# 12V_Converter.net
KiCad netlist of a schematic drawn in Altium Designer
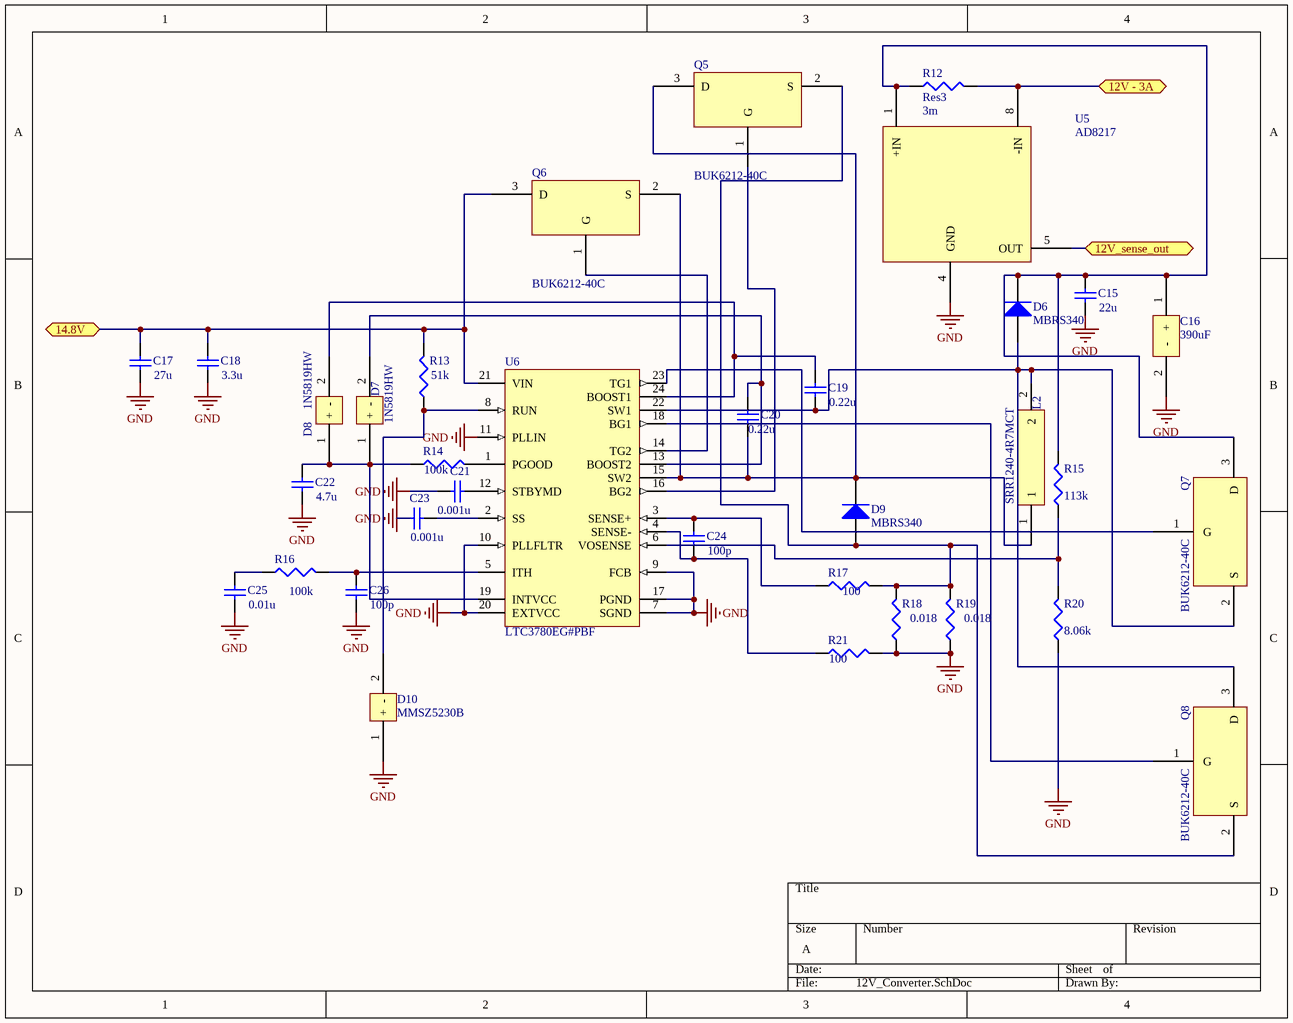
[diagram p0: 12V_Converter.SchDoc]

(export (version "E")
  (design (tool "Eeschema 10.0.6"))
  (components
    (comp (ref "C15")
      (value "22u")
      (footprint "C1206")
      (description "Capacitor (Semiconductor SIM Model)")
      (fields (field (name "Comment") "Cap Semi") (field (name "PUBLISHER") "Altium Limited"))
      (libsource (lib "Miscellaneous Devices") (part "Cap Semi"))
    )
    (comp (ref "C16")
      (value "390uF")
      (footprint "PCV1E391MCL2GS")
      (description "Aluminum Capacitor")
      (libsource (lib "Integrated_Library") (part "PCV1E391MCL2GS"))
    )
    (comp (ref "C17")
      (value "27u")
      (footprint "C1206")
      (description "Capacitor (Semiconductor SIM Model)")
      (fields (field (name "Comment") "Cap Semi") (field (name "PUBLISHER") "Altium Limited"))
      (libsource (lib "Miscellaneous Devices") (part "Cap Semi"))
    )
    (comp (ref "C18")
      (value "3.3u")
      (footprint "C1206")
      (description "Capacitor (Semiconductor SIM Model)")
      (fields (field (name "Comment") "Cap Semi") (field (name "PUBLISHER") "Altium Limited"))
      (libsource (lib "Miscellaneous Devices") (part "Cap Semi"))
    )
    (comp (ref "C19")
      (value "0.22u")
      (footprint "C1206")
      (description "Capacitor (Semiconductor SIM Model)")
      (fields (field (name "Comment") "Cap Semi") (field (name "PUBLISHER") "Altium Limited"))
      (libsource (lib "Miscellaneous Devices") (part "Cap Semi"))
    )
    (comp (ref "C20")
      (value "0.22u")
      (footprint "C1206")
      (description "Capacitor (Semiconductor SIM Model)")
      (fields (field (name "Comment") "Cap Semi") (field (name "PUBLISHER") "Altium Limited"))
      (libsource (lib "Miscellaneous Devices") (part "Cap Semi"))
    )
    (comp (ref "C21")
      (value "0.001u")
      (footprint "C1206")
      (description "Capacitor (Semiconductor SIM Model)")
      (fields (field (name "Comment") "Cap Semi") (field (name "PUBLISHER") "Altium Limited"))
      (libsource (lib "Miscellaneous Devices") (part "Cap Semi"))
    )
    (comp (ref "C22")
      (value "4.7u")
      (footprint "C1206")
      (description "Capacitor (Semiconductor SIM Model)")
      (fields (field (name "Comment") "Cap Semi") (field (name "PUBLISHER") "Altium Limited"))
      (libsource (lib "Miscellaneous Devices") (part "Cap Semi"))
    )
    (comp (ref "C23")
      (value "0.001u")
      (footprint "C1206")
      (description "Capacitor (Semiconductor SIM Model)")
      (fields (field (name "Comment") "Cap Semi") (field (name "PUBLISHER") "Altium Limited"))
      (libsource (lib "Miscellaneous Devices") (part "Cap Semi"))
    )
    (comp (ref "C24")
      (value "100p")
      (footprint "C1206")
      (description "Capacitor (Semiconductor SIM Model)")
      (fields (field (name "Comment") "Cap Semi") (field (name "PUBLISHER") "Altium Limited"))
      (libsource (lib "Miscellaneous Devices") (part "Cap Semi"))
    )
    (comp (ref "C25")
      (value "0.01u")
      (footprint "C1206")
      (description "Capacitor (Semiconductor SIM Model)")
      (fields (field (name "Comment") "Cap Semi") (field (name "PUBLISHER") "Altium Limited"))
      (libsource (lib "Miscellaneous Devices") (part "Cap Semi"))
    )
    (comp (ref "C26")
      (value "100p")
      (footprint "C1206")
      (description "Capacitor (Semiconductor SIM Model)")
      (fields (field (name "Comment") "Cap Semi") (field (name "PUBLISHER") "Altium Limited"))
      (libsource (lib "Miscellaneous Devices") (part "Cap Semi"))
    )
    (comp (ref "D6")
      (value "MBRS340")
      (footprint "SMC")
      (description "Default Diode")
      (fields (field (name "PUBLISHER") "Altium Limited"))
      (libsource (lib "Miscellaneous Devices") (part "Diode"))
    )
    (comp (ref "D7")
      (value "1N5819HW")
      (footprint "1N5819HW")
      (description "1A Schottky Barrier Rectifier")
      (libsource (lib "Integrated_Library") (part "1N5819HW"))
    )
    (comp (ref "D8")
      (value "1N5819HW")
      (footprint "1N5819HW")
      (description "1A Schottky Barrier Rectifier")
      (libsource (lib "Integrated_Library") (part "1N5819HW"))
    )
    (comp (ref "D9")
      (value "MBRS340")
      (footprint "SMC")
      (description "Default Diode")
      (fields (field (name "PUBLISHER") "Altium Limited"))
      (libsource (lib "Miscellaneous Devices") (part "Diode"))
    )
    (comp (ref "D10")
      (value "MMSZ5230B")
      (footprint "MMSZ5230B")
      (description "Zener Diode")
      (libsource (lib "Integrated_Library") (part "MMSZ5230B"))
    )
    (comp (ref "L2")
      (value "SRR1240-4R7MCT")
      (footprint "SRR1240-4R7M")
      (description "Inductor")
      (libsource (lib "Integrated_Library") (part "SRR1240-4R7MCT"))
    )
    (comp (ref "Q5")
      (value "BUK6212-40C")
      (footprint "BUK6212-40C")
      (description "N-Channel TrenchMOS Intermediate Level FET")
      (libsource (lib "Integrated_Library") (part "BUK6212-40C"))
    )
    (comp (ref "Q6")
      (value "BUK6212-40C")
      (footprint "BUK6212-40C")
      (description "N-Channel TrenchMOS Intermediate Level FET")
      (libsource (lib "Integrated_Library") (part "BUK6212-40C"))
    )
    (comp (ref "Q7")
      (value "BUK6212-40C")
      (footprint "BUK6212-40C")
      (description "N-Channel TrenchMOS Intermediate Level FET")
      (libsource (lib "") (part "BUK6212-40C_1"))
    )
    (comp (ref "Q8")
      (value "BUK6212-40C")
      (footprint "BUK6212-40C")
      (description "N-Channel TrenchMOS Intermediate Level FET")
      (libsource (lib "") (part "BUK6212-40C_1"))
    )
    (comp (ref "R12")
      (value "Res3")
      (footprint "14-1210")
      (description "Resistor")
      (fields (field (name "ALTIUM_VALUE") "3m") (field (name "PUBLISHER") "Altium Limited"))
      (libsource (lib "Miscellaneous Devices") (part "Res3"))
    )
    (comp (ref "R13")
      (value "51k")
      (footprint "J1-0603")
      (description "Resistor")
      (fields (field (name "Comment") "Res3") (field (name "PUBLISHER") "Altium Limited"))
      (libsource (lib "Miscellaneous Devices") (part "Res3"))
    )
    (comp (ref "R14")
      (value "100k")
      (footprint "J1-0603")
      (description "Resistor")
      (fields (field (name "Comment") "Res3") (field (name "PUBLISHER") "Altium Limited"))
      (libsource (lib "Miscellaneous Devices") (part "Res3"))
    )
    (comp (ref "R15")
      (value "113k")
      (footprint "J1-0603")
      (description "Resistor")
      (fields (field (name "Comment") "Res3") (field (name "PUBLISHER") "Altium Limited"))
      (libsource (lib "Miscellaneous Devices") (part "Res3"))
    )
    (comp (ref "R16")
      (value "100k")
      (footprint "J1-0603")
      (description "Resistor")
      (fields (field (name "Comment") "Res3") (field (name "PUBLISHER") "Altium Limited"))
      (libsource (lib "Miscellaneous Devices") (part "Res3"))
    )
    (comp (ref "R17")
      (value "100")
      (footprint "J1-0603")
      (description "Resistor")
      (fields (field (name "Comment") "Res3") (field (name "PUBLISHER") "Altium Limited"))
      (libsource (lib "Miscellaneous Devices") (part "Res3"))
    )
    (comp (ref "R18")
      (value "0.018")
      (footprint "J1-0603")
      (description "Resistor")
      (fields (field (name "Comment") "Res3") (field (name "PUBLISHER") "Altium Limited"))
      (libsource (lib "Miscellaneous Devices") (part "Res3"))
    )
    (comp (ref "R19")
      (value "0.018")
      (footprint "J1-0603")
      (description "Resistor")
      (fields (field (name "Comment") "Res3") (field (name "PUBLISHER") "Altium Limited"))
      (libsource (lib "Miscellaneous Devices") (part "Res3"))
    )
    (comp (ref "R20")
      (value "8.06k")
      (footprint "J1-0603")
      (description "Resistor")
      (fields (field (name "Comment") "Res3") (field (name "PUBLISHER") "Altium Limited"))
      (libsource (lib "Miscellaneous Devices") (part "Res3"))
    )
    (comp (ref "R21")
      (value "100")
      (footprint "J1-0603")
      (description "Resistor")
      (fields (field (name "Comment") "Res3") (field (name "PUBLISHER") "Altium Limited"))
      (libsource (lib "Miscellaneous Devices") (part "Res3"))
    )
    (comp (ref "U5")
      (value "AD8217")
      (footprint "AD8217")
      (description "Current Shunt Moniter")
      (libsource (lib "Integrated_Library") (part "AD8217"))
    )
    (comp (ref "U6")
      (value "LTC3780EG#PBF")
      (footprint "LTC3780 24-Leaqd Plastic SSOP")
      (fields (field (name "MANUFACTURER") "Linear Technology"))
      (libsource (lib "Integrated_Library") (part "LTC3780EG#PBF"))
    )
  )
  (nets
    (net (code "1") (name "/12V - 3A") (class "Default")
      (node (ref "R12") (pin "2") (pinfunction "2_2") (pintype "passive"))
      (node (ref "U5") (pin "8") (pinfunction "-IN_8") (pintype "passive"))
    )
    (net (code "2") (name "/12V_sense_out") (class "Default")
      (node (ref "U5") (pin "5") (pinfunction "OUT_5") (pintype "passive"))
    )
    (net (code "3") (name "/14.8V") (class "Default")
      (node (ref "C17") (pin "2") (pinfunction "2_2") (pintype "passive"))
      (node (ref "C18") (pin "2") (pinfunction "2_2") (pintype "passive"))
      (node (ref "Q6") (pin "3") (pinfunction "D_3") (pintype "passive"))
      (node (ref "R13") (pin "2") (pinfunction "2_2") (pintype "passive"))
      (node (ref "U6") (pin "21") (pinfunction "VIN_21") (pintype "power_in"))
    )
    (net (code "4") (name "GND") (class "Default")
      (node (ref "C15") (pin "1") (pinfunction "1_1") (pintype "passive"))
      (node (ref "C16") (pin "2") (pinfunction "-_2") (pintype "passive"))
      (node (ref "C17") (pin "1") (pinfunction "1_1") (pintype "passive"))
      (node (ref "C18") (pin "1") (pinfunction "1_1") (pintype "passive"))
      (node (ref "C21") (pin "1") (pinfunction "1_1") (pintype "passive"))
      (node (ref "C22") (pin "1") (pinfunction "1_1") (pintype "passive"))
      (node (ref "C23") (pin "1") (pinfunction "1_1") (pintype "passive"))
      (node (ref "C25") (pin "1") (pinfunction "1_1") (pintype "passive"))
      (node (ref "C26") (pin "1") (pinfunction "1_1") (pintype "passive"))
      (node (ref "D10") (pin "1") (pinfunction "+_1") (pintype "passive"))
      (node (ref "R18") (pin "1") (pinfunction "1_1") (pintype "passive"))
      (node (ref "R19") (pin "1") (pinfunction "1_1") (pintype "passive"))
      (node (ref "R20") (pin "1") (pinfunction "1_1") (pintype "passive"))
      (node (ref "R21") (pin "2") (pinfunction "2_2") (pintype "passive"))
      (node (ref "U5") (pin "4") (pinfunction "GND_4") (pintype "passive"))
      (node (ref "U6") (pin "10") (pinfunction "PLLFLTR_10") (pintype "input"))
      (node (ref "U6") (pin "11") (pinfunction "PLLIN_11") (pintype "input"))
      (node (ref "U6") (pin "17") (pinfunction "PGND_17") (pintype "power_in"))
      (node (ref "U6") (pin "20") (pinfunction "EXTVCC_20") (pintype "power_in"))
      (node (ref "U6") (pin "7") (pinfunction "SGND_7") (pintype "power_in"))
      (node (ref "U6") (pin "9") (pinfunction "FCB_9") (pintype "input"))
    )
    (net (code "5") (name "Net-(C16-+)") (class "Default")
      (node (ref "C15") (pin "2") (pinfunction "2_2") (pintype "passive"))
      (node (ref "C16") (pin "1") (pinfunction "+_1") (pintype "passive"))
      (node (ref "D6") (pin "2") (pinfunction "K_2") (pintype "passive"))
      (node (ref "Q7") (pin "3") (pinfunction "D_3") (pintype "passive"))
      (node (ref "R12") (pin "1") (pinfunction "1_1") (pintype "passive"))
      (node (ref "R15") (pin "2") (pinfunction "2_2") (pintype "passive"))
      (node (ref "U5") (pin "1") (pinfunction "+IN_1") (pintype "passive"))
    )
    (net (code "6") (name "Net-(C25-Pad2)") (class "Default")
      (node (ref "C25") (pin "2") (pinfunction "2_2") (pintype "passive"))
      (node (ref "R16") (pin "1") (pinfunction "1_1") (pintype "passive"))
    )
    (net (code "7") (name "Net-(D6-A)") (class "Default")
      (node (ref "C19") (pin "1") (pinfunction "1_1") (pintype "passive"))
      (node (ref "D6") (pin "1") (pinfunction "A_1") (pintype "passive"))
      (node (ref "L2") (pin "2") (pinfunction "2_2") (pintype "passive"))
      (node (ref "Q7") (pin "2") (pinfunction "S_2") (pintype "passive"))
      (node (ref "Q8") (pin "3") (pinfunction "D_3") (pintype "passive"))
      (node (ref "U6") (pin "22") (pinfunction "SW1_22") (pintype "passive"))
    )
    (net (code "8") (name "Net-(D7-+)") (class "Default")
      (node (ref "C22") (pin "2") (pinfunction "2_2") (pintype "passive"))
      (node (ref "D7") (pin "1") (pinfunction "+_1") (pintype "passive"))
      (node (ref "D8") (pin "1") (pinfunction "+_1") (pintype "passive"))
      (node (ref "R14") (pin "1") (pinfunction "1_1") (pintype "passive"))
      (node (ref "U6") (pin "19") (pinfunction "INTVCC_19") (pintype "power_in"))
    )
    (net (code "9") (name "Net-(D7--)") (class "Default")
      (node (ref "C20") (pin "2") (pinfunction "2_2") (pintype "passive"))
      (node (ref "D7") (pin "2") (pinfunction "-_2") (pintype "passive"))
      (node (ref "U6") (pin "13") (pinfunction "BOOST2_13") (pintype "passive"))
    )
    (net (code "10") (name "Net-(D8--)") (class "Default")
      (node (ref "C19") (pin "2") (pinfunction "2_2") (pintype "passive"))
      (node (ref "D8") (pin "2") (pinfunction "-_2") (pintype "passive"))
      (node (ref "U6") (pin "24") (pinfunction "BOOST1_24") (pintype "passive"))
    )
    (net (code "11") (name "Net-(D9-A)") (class "Default")
      (node (ref "D9") (pin "1") (pinfunction "A_1") (pintype "passive"))
      (node (ref "Q5") (pin "2") (pinfunction "S_2") (pintype "passive"))
      (node (ref "Q8") (pin "2") (pinfunction "S_2") (pintype "passive"))
      (node (ref "R17") (pin "2") (pinfunction "2_2") (pintype "passive"))
      (node (ref "R18") (pin "2") (pinfunction "2_2") (pintype "passive"))
      (node (ref "R19") (pin "2") (pinfunction "2_2") (pintype "passive"))
    )
    (net (code "12") (name "Net-(D9-K)") (class "Default")
      (node (ref "C20") (pin "1") (pinfunction "1_1") (pintype "passive"))
      (node (ref "D9") (pin "2") (pinfunction "K_2") (pintype "passive"))
      (node (ref "L2") (pin "1") (pinfunction "1_1") (pintype "passive"))
      (node (ref "Q5") (pin "3") (pinfunction "D_3") (pintype "passive"))
      (node (ref "Q6") (pin "2") (pinfunction "S_2") (pintype "passive"))
      (node (ref "U6") (pin "15") (pinfunction "SW2_15") (pintype "passive"))
    )
    (net (code "13") (name "Net-(D10--)") (class "Default")
      (node (ref "D10") (pin "2") (pinfunction "-_2") (pintype "passive"))
      (node (ref "R13") (pin "1") (pinfunction "1_1") (pintype "passive"))
      (node (ref "U6") (pin "8") (pinfunction "RUN_8") (pintype "input"))
    )
    (net (code "14") (name "Net-(Q5-G)") (class "Default")
      (node (ref "Q5") (pin "1") (pinfunction "G_1") (pintype "passive"))
      (node (ref "U6") (pin "16") (pinfunction "BG2_16") (pintype "output"))
    )
    (net (code "15") (name "Net-(Q6-G)") (class "Default")
      (node (ref "Q6") (pin "1") (pinfunction "G_1") (pintype "passive"))
      (node (ref "U6") (pin "14") (pinfunction "TG2_14") (pintype "output"))
    )
    (net (code "16") (name "Net-(Q7-G)") (class "Default")
      (node (ref "Q7") (pin "1") (pinfunction "G_1") (pintype "passive"))
      (node (ref "U6") (pin "23") (pinfunction "TG1_23") (pintype "output"))
    )
    (net (code "17") (name "Net-(Q8-G)") (class "Default")
      (node (ref "Q8") (pin "1") (pinfunction "G_1") (pintype "passive"))
      (node (ref "U6") (pin "18") (pinfunction "BG1_18") (pintype "output"))
    )
    (net (code "18") (name "Net-(U6-ITH)") (class "Default")
      (node (ref "C26") (pin "2") (pinfunction "2_2") (pintype "passive"))
      (node (ref "R16") (pin "2") (pinfunction "2_2") (pintype "passive"))
      (node (ref "U6") (pin "5") (pinfunction "ITH_5") (pintype "passive"))
    )
    (net (code "19") (name "Net-(U6-PGOOD)") (class "Default")
      (node (ref "R14") (pin "2") (pinfunction "2_2") (pintype "passive"))
      (node (ref "U6") (pin "1") (pinfunction "PGOOD_1") (pintype "open_collector"))
    )
    (net (code "20") (name "Net-(U6-SENSE+)") (class "Default")
      (node (ref "C24") (pin "2") (pinfunction "2_2") (pintype "passive"))
      (node (ref "R17") (pin "1") (pinfunction "1_1") (pintype "passive"))
      (node (ref "U6") (pin "3") (pinfunction "SENSE+_3") (pintype "input"))
    )
    (net (code "21") (name "Net-(U6-SENSE-)") (class "Default")
      (node (ref "C24") (pin "1") (pinfunction "1_1") (pintype "passive"))
      (node (ref "R21") (pin "1") (pinfunction "1_1") (pintype "passive"))
      (node (ref "U6") (pin "4") (pinfunction "SENSE-_4") (pintype "input"))
    )
    (net (code "22") (name "Net-(U6-SS)") (class "Default")
      (node (ref "C23") (pin "2") (pinfunction "2_2") (pintype "passive"))
      (node (ref "U6") (pin "2") (pinfunction "SS_2") (pintype "input"))
    )
    (net (code "23") (name "Net-(U6-STBYMD)") (class "Default")
      (node (ref "C21") (pin "2") (pinfunction "2_2") (pintype "passive"))
      (node (ref "U6") (pin "12") (pinfunction "STBYMD_12") (pintype "input"))
    )
    (net (code "24") (name "Net-(U6-VOSENSE)") (class "Default")
      (node (ref "R15") (pin "1") (pinfunction "1_1") (pintype "passive"))
      (node (ref "R20") (pin "2") (pinfunction "2_2") (pintype "passive"))
      (node (ref "U6") (pin "6") (pinfunction "VOSENSE_6") (pintype "input"))
    )
  )
)
